# SCH_BlinkyBlinky_2025-11-07.net
KiCad netlist of a schematic drawn in EasyEDA
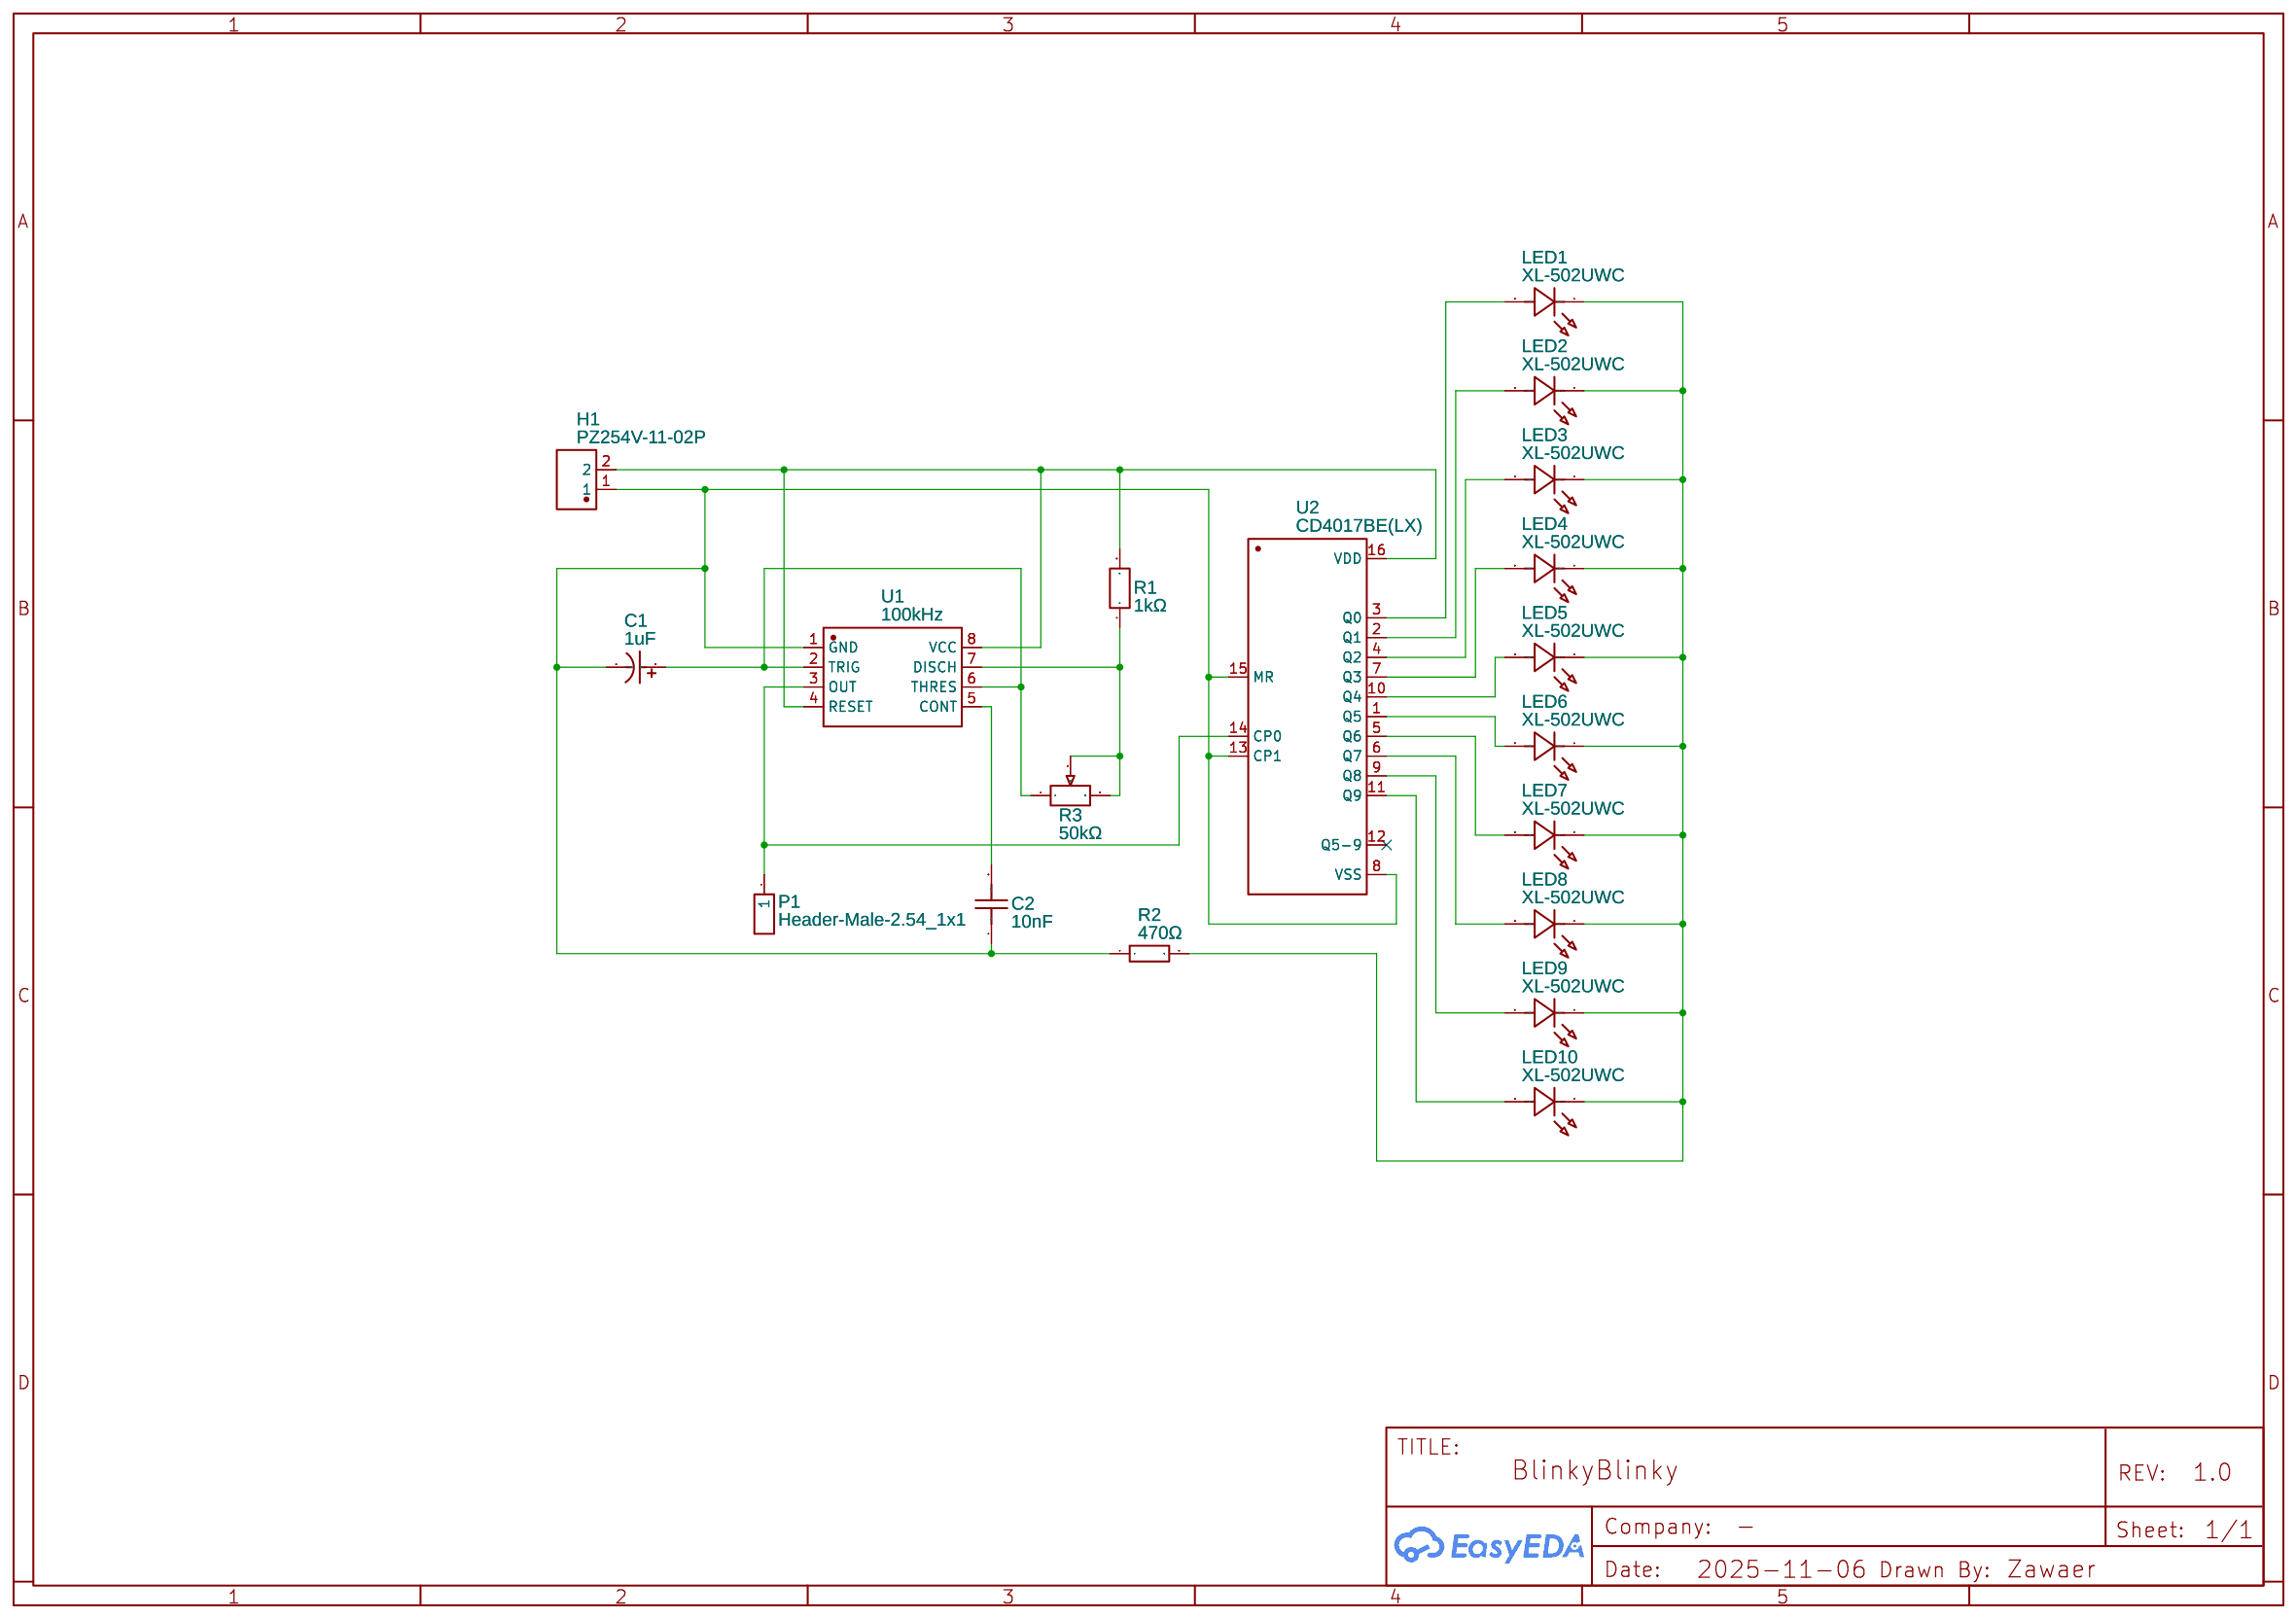
[diagram p0: schematic sheet]

(export (version "E")
  (design (tool "Eeschema 10.0.6"))
  (components
    (comp (ref "C1")
      (value "1uF")
      (fields (field (name "Manufacturer Part") "KF010M050C110A") (field (name "Manufacturer") "CapXon(丰宾)"))
      (libsource (lib "") (part "KF010M050C110A"))
    )
    (comp (ref "C2")
      (value "10nF")
      (fields (field (name "Manufacturer Part") "N09F1B103MN0B0S0N0") (field (name "Manufacturer") "STE(松田)"))
      (libsource (lib "") (part "N09F1B103MN0B0S0N0"))
    )
    (comp (ref "H1")
      (value "PZ254V-11-02P")
      (fields (field (name "Manufacturer") "XFCN(兴飞)"))
      (libsource (lib "") (part "PZ254V-11-02P"))
    )
    (comp (ref "LED1")
      (value "XL-502UWC")
      (fields (field (name "Manufacturer") "XINGLIGHT(成兴光)"))
      (libsource (lib "") (part "XL-502UWC"))
    )
    (comp (ref "LED2")
      (value "XL-502UWC")
      (fields (field (name "Manufacturer") "XINGLIGHT(成兴光)"))
      (libsource (lib "") (part "XL-502UWC"))
    )
    (comp (ref "LED3")
      (value "XL-502UWC")
      (fields (field (name "Manufacturer") "XINGLIGHT(成兴光)"))
      (libsource (lib "") (part "XL-502UWC"))
    )
    (comp (ref "LED4")
      (value "XL-502UWC")
      (fields (field (name "Manufacturer") "XINGLIGHT(成兴光)"))
      (libsource (lib "") (part "XL-502UWC"))
    )
    (comp (ref "LED5")
      (value "XL-502UWC")
      (fields (field (name "Manufacturer") "XINGLIGHT(成兴光)"))
      (libsource (lib "") (part "XL-502UWC"))
    )
    (comp (ref "LED6")
      (value "XL-502UWC")
      (fields (field (name "Manufacturer") "XINGLIGHT(成兴光)"))
      (libsource (lib "") (part "XL-502UWC"))
    )
    (comp (ref "LED7")
      (value "XL-502UWC")
      (fields (field (name "Manufacturer") "XINGLIGHT(成兴光)"))
      (libsource (lib "") (part "XL-502UWC"))
    )
    (comp (ref "LED8")
      (value "XL-502UWC")
      (fields (field (name "Manufacturer") "XINGLIGHT(成兴光)"))
      (libsource (lib "") (part "XL-502UWC"))
    )
    (comp (ref "LED9")
      (value "XL-502UWC")
      (fields (field (name "Manufacturer") "XINGLIGHT(成兴光)"))
      (libsource (lib "") (part "XL-502UWC"))
    )
    (comp (ref "LED10")
      (value "XL-502UWC")
      (fields (field (name "Manufacturer") "XINGLIGHT(成兴光)"))
      (libsource (lib "") (part "XL-502UWC"))
    )
    (comp (ref "P1")
      (value "Header-Male-2.54_1x1")
      (fields (field (name "Manufacturer Part") "2.54-1*1P针") (field (name "Manufacturer") "BOOMELE(博穆精密)"))
      (libsource (lib "") (part "Header-Male-2.54_1x1"))
    )
    (comp (ref "R1")
      (value "1kΩ")
      (fields (field (name "Manufacturer Part") "MF1/4W-1KΩ±1%T52") (field (name "Manufacturer") "华星机电"))
      (libsource (lib "") (part "MF1/4W-1KΩ±1%T52"))
    )
    (comp (ref "R2")
      (value "470Ω")
      (fields
        (field (name "Manufacturer Part") "MFR0W4F4700A50")
        (field (name "Manufacturer") "UNI-ROYAL(厚声)")
      )
      (libsource (lib "") (part "MFR0W4F4700A50"))
    )
    (comp (ref "R3")
      (value "50kΩ")
      (fields (field (name "Manufacturer Part") "3296X-1-503") (field (name "Manufacturer") "BOCHEN(博晨)"))
      (libsource (lib "") (part "3296X-1-503_C118912"))
    )
    (comp (ref "U1")
      (value "100kHz")
      (fields (field (name "Manufacturer Part") "NE555P") (field (name "Manufacturer") "TI(德州仪器)"))
      (libsource (lib "") (part "NE555P"))
    )
    (comp (ref "U2")
      (value "CD4017BE(LX)")
      (fields (field (name "Manufacturer") "LX(灵星芯微)"))
      (libsource (lib "") (part "CD4017BE(LX)"))
    )
  )
  (nets
    (net (code "1") (name "Net-(LED1-A)") (class "Default")
      (node (ref "LED1") (pin "2") (pinfunction "A_2") (pintype "unspecified"))
      (node (ref "U2") (pin "3") (pinfunction "Q0_3") (pintype "unspecified"))
    )
    (net (code "2") (name "Net-(LED1-K)") (class "Default")
      (node (ref "LED1") (pin "1") (pinfunction "K_1") (pintype "unspecified"))
      (node (ref "LED10") (pin "1") (pinfunction "K_1") (pintype "unspecified"))
      (node (ref "LED2") (pin "1") (pinfunction "K_1") (pintype "unspecified"))
      (node (ref "LED3") (pin "1") (pinfunction "K_1") (pintype "unspecified"))
      (node (ref "LED4") (pin "1") (pinfunction "K_1") (pintype "unspecified"))
      (node (ref "LED5") (pin "1") (pinfunction "K_1") (pintype "unspecified"))
      (node (ref "LED6") (pin "1") (pinfunction "K_1") (pintype "unspecified"))
      (node (ref "LED7") (pin "1") (pinfunction "K_1") (pintype "unspecified"))
      (node (ref "LED8") (pin "1") (pinfunction "K_1") (pintype "unspecified"))
      (node (ref "LED9") (pin "1") (pinfunction "K_1") (pintype "unspecified"))
      (node (ref "R2") (pin "2") (pinfunction "2_2") (pintype "input"))
    )
    (net (code "3") (name "Net-(LED2-A)") (class "Default")
      (node (ref "LED2") (pin "2") (pinfunction "A_2") (pintype "unspecified"))
      (node (ref "U2") (pin "2") (pinfunction "Q1_2") (pintype "unspecified"))
    )
    (net (code "4") (name "Net-(LED3-A)") (class "Default")
      (node (ref "LED3") (pin "2") (pinfunction "A_2") (pintype "unspecified"))
      (node (ref "U2") (pin "4") (pinfunction "Q2_4") (pintype "unspecified"))
    )
    (net (code "5") (name "Net-(LED4-A)") (class "Default")
      (node (ref "LED4") (pin "2") (pinfunction "A_2") (pintype "unspecified"))
      (node (ref "U2") (pin "7") (pinfunction "Q3_7") (pintype "unspecified"))
    )
    (net (code "6") (name "Net-(LED5-A)") (class "Default")
      (node (ref "LED5") (pin "2") (pinfunction "A_2") (pintype "unspecified"))
      (node (ref "U2") (pin "10") (pinfunction "Q4_10") (pintype "unspecified"))
    )
    (net (code "7") (name "Net-(LED6-A)") (class "Default")
      (node (ref "LED6") (pin "2") (pinfunction "A_2") (pintype "unspecified"))
      (node (ref "U2") (pin "1") (pinfunction "Q5_1") (pintype "unspecified"))
    )
    (net (code "8") (name "Net-(LED7-A)") (class "Default")
      (node (ref "LED7") (pin "2") (pinfunction "A_2") (pintype "unspecified"))
      (node (ref "U2") (pin "5") (pinfunction "Q6_5") (pintype "unspecified"))
    )
    (net (code "9") (name "Net-(LED8-A)") (class "Default")
      (node (ref "LED8") (pin "2") (pinfunction "A_2") (pintype "unspecified"))
      (node (ref "U2") (pin "6") (pinfunction "Q7_6") (pintype "unspecified"))
    )
    (net (code "10") (name "Net-(LED9-A)") (class "Default")
      (node (ref "LED9") (pin "2") (pinfunction "A_2") (pintype "unspecified"))
      (node (ref "U2") (pin "9") (pinfunction "Q8_9") (pintype "unspecified"))
    )
    (net (code "11") (name "Net-(LED10-A)") (class "Default")
      (node (ref "LED10") (pin "2") (pinfunction "A_2") (pintype "unspecified"))
      (node (ref "U2") (pin "11") (pinfunction "Q9_11") (pintype "unspecified"))
    )
    (net (code "12") (name "Net-(U1-CONT)") (class "Default")
      (node (ref "C2") (pin "2") (pinfunction "2_2") (pintype "unspecified"))
      (node (ref "U1") (pin "5") (pinfunction "CONT_5") (pintype "unspecified"))
    )
    (net (code "13") (name "Net-(U1-DISCH)") (class "Default")
      (node (ref "R1") (pin "1") (pinfunction "1_1") (pintype "unspecified"))
      (node (ref "R3") (pin "2") (pinfunction "2_2") (pintype "input"))
      (node (ref "R3") (pin "3") (pinfunction "3_3") (pintype "input"))
      (node (ref "U1") (pin "7") (pinfunction "DISCH_7") (pintype "unspecified"))
    )
    (net (code "14") (name "Net-(U1-GND)") (class "Default")
      (node (ref "C1") (pin "2") (pinfunction "2_2") (pintype "input"))
      (node (ref "C2") (pin "1") (pinfunction "1_1") (pintype "unspecified"))
      (node (ref "H1") (pin "1") (pinfunction "1_1") (pintype "unspecified"))
      (node (ref "R2") (pin "1") (pinfunction "1_1") (pintype "input"))
      (node (ref "U1") (pin "1") (pinfunction "GND_1") (pintype "unspecified"))
      (node (ref "U2") (pin "13") (pinfunction "CP1_13") (pintype "unspecified"))
      (node (ref "U2") (pin "15") (pinfunction "MR_15") (pintype "unspecified"))
      (node (ref "U2") (pin "8") (pinfunction "VSS_8") (pintype "unspecified"))
    )
    (net (code "15") (name "Net-(U1-OUT)") (class "Default")
      (node (ref "P1") (pin "1") (pinfunction "1_1") (pintype "input"))
      (node (ref "U1") (pin "3") (pinfunction "OUT_3") (pintype "unspecified"))
      (node (ref "U2") (pin "14") (pinfunction "CP0_14") (pintype "unspecified"))
    )
    (net (code "16") (name "Net-(U1-RESET)") (class "Default")
      (node (ref "H1") (pin "2") (pinfunction "2_2") (pintype "unspecified"))
      (node (ref "R1") (pin "2") (pinfunction "2_2") (pintype "unspecified"))
      (node (ref "U1") (pin "4") (pinfunction "RESET_4") (pintype "unspecified"))
      (node (ref "U1") (pin "8") (pinfunction "VCC_8") (pintype "unspecified"))
      (node (ref "U2") (pin "16") (pinfunction "VDD_16") (pintype "unspecified"))
    )
    (net (code "17") (name "Net-(U1-THRES)") (class "Default")
      (node (ref "C1") (pin "1") (pinfunction "1_1") (pintype "input"))
      (node (ref "R3") (pin "1") (pinfunction "1_1") (pintype "input"))
      (node (ref "U1") (pin "2") (pinfunction "TRIG_2") (pintype "unspecified"))
      (node (ref "U1") (pin "6") (pinfunction "THRES_6") (pintype "unspecified"))
    )
    (net (code "18") (name "unconnected-(U2-Q5-9-Pad12)") (class "Default")
      (node (ref "U2") (pin "12") (pinfunction "Q5-9_12") (pintype "unspecified+no_connect"))
    )
  )
)
